# r0ndL-HPMountsPlus.net
KiCad netlist of a schematic drawn in EAGLE
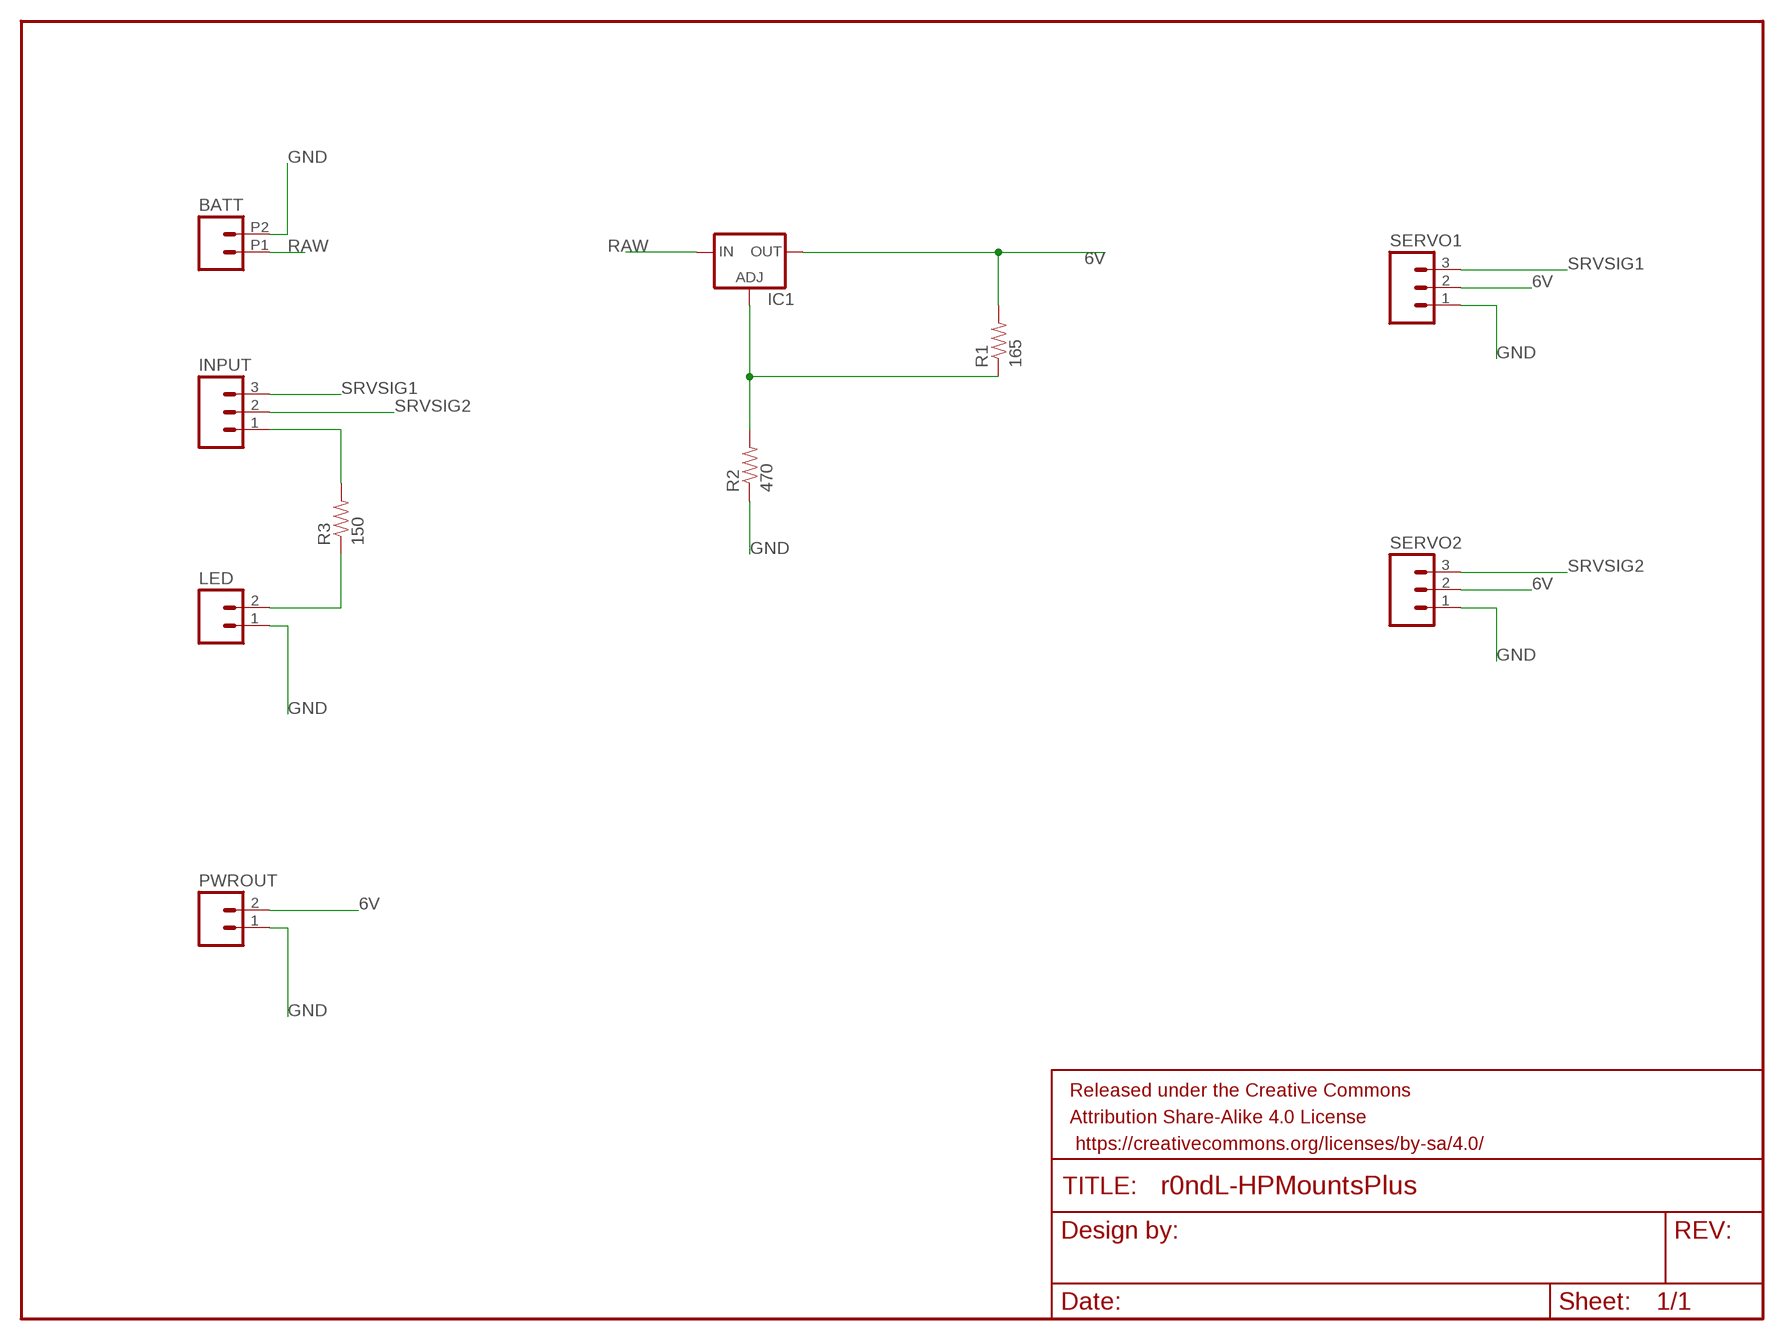
[diagram p0: schematic, sheet 1]

(export (version "E")
  (design (tool "Eeschema 10.0.6"))
  (components
    (comp (ref "BATT")
      (value "M022.54MM_SCREWTERM")
      (footprint "eagle-import:1X02_2.54_SCREWTERM")
      (libsource (lib "eagle-import") (part "M022.54MM_SCREWTERM"))
    )
    (comp (ref "FRAME1")
      (value "FRAME-LETTER")
      (footprint "eagle-import:CREATIVE_COMMONS")
      (libsource (lib "eagle-import") (part "FRAME-LETTER"))
    )
    (comp (ref "IC1")
      (value "LM317TS")
      (footprint "eagle-import:317TS")
      (libsource (lib "eagle-import") (part "LM317TS"))
    )
    (comp (ref "INPUT")
      (value "M03PTH")
      (footprint "eagle-import:1X03")
      (libsource (lib "eagle-import") (part "M03PTH"))
    )
    (comp (ref "LED")
      (value "M02PTH")
      (footprint "eagle-import:1X02")
      (libsource (lib "eagle-import") (part "M02PTH"))
    )
    (comp (ref "PWROUT")
      (value "M02PTH")
      (footprint "eagle-import:1X02")
      (libsource (lib "eagle-import") (part "M02PTH"))
    )
    (comp (ref "R1")
      (value "165")
      (footprint "eagle-import:AXIAL-0.4")
      (libsource (lib "eagle-import") (part "RESISTORPTH-1/4W"))
    )
    (comp (ref "R2")
      (value "470")
      (footprint "eagle-import:AXIAL-0.4")
      (libsource (lib "eagle-import") (part "RESISTORPTH-1/4W"))
    )
    (comp (ref "R3")
      (value "150")
      (footprint "eagle-import:AXIAL-0.4")
      (libsource (lib "eagle-import") (part "RESISTORPTH-1/4W"))
    )
    (comp (ref "SERVO1")
      (value "M03PTH")
      (footprint "eagle-import:1X03")
      (libsource (lib "eagle-import") (part "M03PTH"))
    )
    (comp (ref "SERVO2")
      (value "M03PTH")
      (footprint "eagle-import:1X03")
      (libsource (lib "eagle-import") (part "M03PTH"))
    )
  )
  (nets
    (net (code "1") (name "/6V") (class "Default")
      (node (ref "IC1") (pin "2") (pinfunction "OUT_2") (pintype "passive"))
      (node (ref "PWROUT") (pin "2") (pinfunction "2_2") (pintype "passive"))
      (node (ref "R1") (pin "P$2") (pinfunction "2_P$2") (pintype "passive"))
      (node (ref "SERVO1") (pin "2") (pinfunction "2_2") (pintype "passive"))
      (node (ref "SERVO2") (pin "2") (pinfunction "2_2") (pintype "passive"))
    )
    (net (code "2") (name "/GND") (class "Default")
      (node (ref "BATT") (pin "P2") (pinfunction "2_P2") (pintype "passive"))
      (node (ref "LED") (pin "1") (pinfunction "1_1") (pintype "passive"))
      (node (ref "PWROUT") (pin "1") (pinfunction "1_1") (pintype "passive"))
      (node (ref "R2") (pin "P$1") (pinfunction "1_P$1") (pintype "passive"))
      (node (ref "SERVO1") (pin "1") (pinfunction "1_1") (pintype "passive"))
      (node (ref "SERVO2") (pin "1") (pinfunction "1_1") (pintype "passive"))
    )
    (net (code "3") (name "/RAW") (class "Default")
      (node (ref "BATT") (pin "P1") (pinfunction "1_P1") (pintype "passive"))
      (node (ref "IC1") (pin "3") (pinfunction "IN_3") (pintype "input"))
    )
    (net (code "4") (name "/SRVSIG1") (class "Default")
      (node (ref "INPUT") (pin "3") (pinfunction "3_3") (pintype "passive"))
      (node (ref "SERVO1") (pin "3") (pinfunction "3_3") (pintype "passive"))
    )
    (net (code "5") (name "/SRVSIG2") (class "Default")
      (node (ref "INPUT") (pin "2") (pinfunction "2_2") (pintype "passive"))
      (node (ref "SERVO2") (pin "3") (pinfunction "3_3") (pintype "passive"))
    )
    (net (code "6") (name "Net-(IC1-ADJ)") (class "Default")
      (node (ref "IC1") (pin "1") (pinfunction "ADJ_1") (pintype "input"))
      (node (ref "R1") (pin "P$1") (pinfunction "1_P$1") (pintype "passive"))
      (node (ref "R2") (pin "P$2") (pinfunction "2_P$2") (pintype "passive"))
    )
    (net (code "7") (name "Net-(R3-1)") (class "Default")
      (node (ref "LED") (pin "2") (pinfunction "2_2") (pintype "passive"))
      (node (ref "R3") (pin "P$1") (pinfunction "1_P$1") (pintype "passive"))
    )
    (net (code "8") (name "Net-(R3-2)") (class "Default")
      (node (ref "INPUT") (pin "1") (pinfunction "1_1") (pintype "passive"))
      (node (ref "R3") (pin "P$2") (pinfunction "2_P$2") (pintype "passive"))
    )
  )
)
